# data_acqsation_system.net
KiCad netlist of a schematic drawn in EAGLE
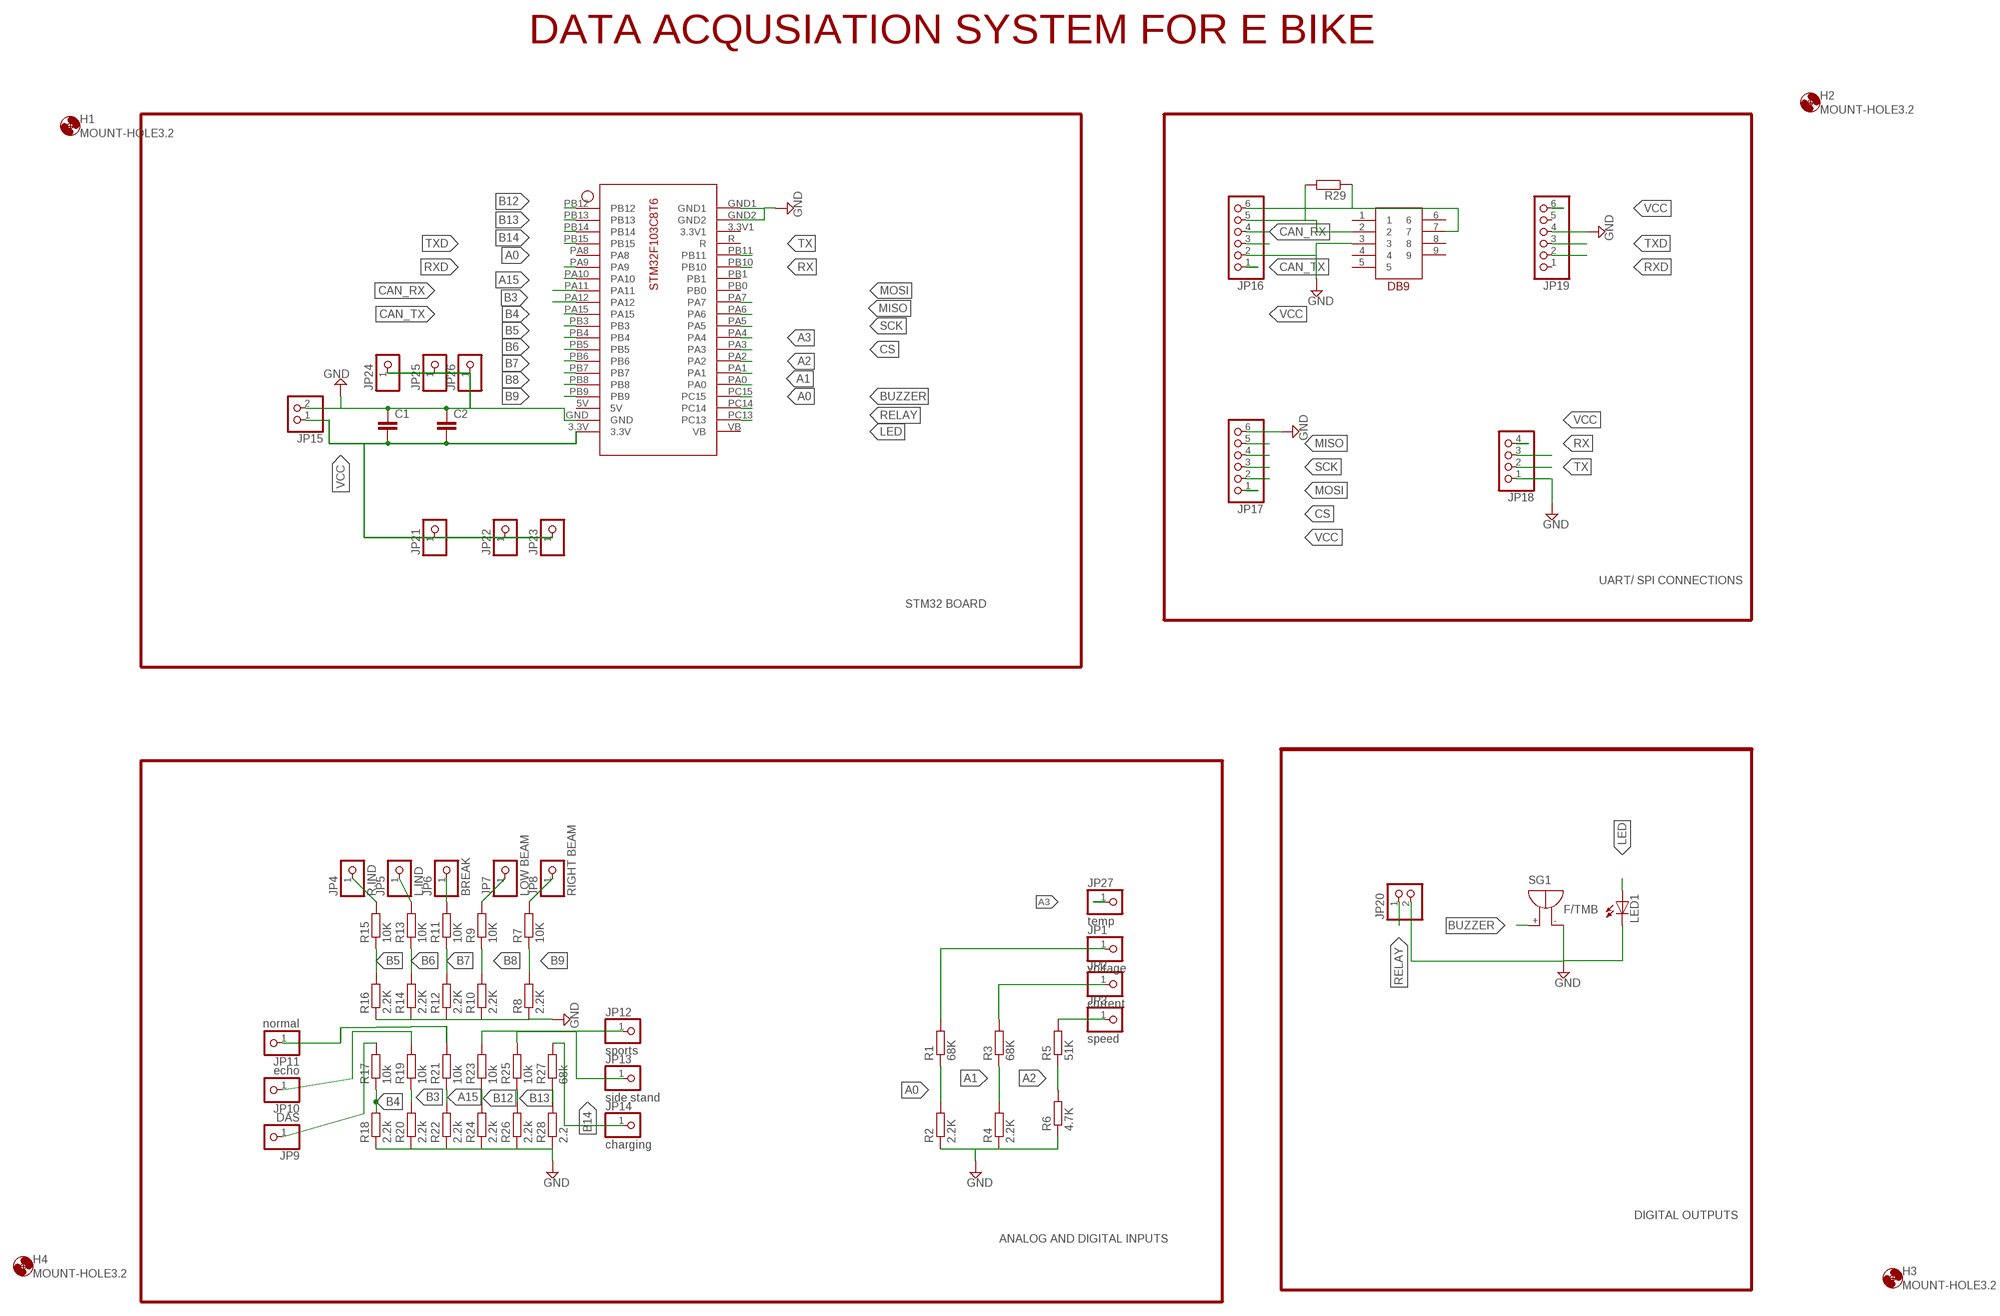
[diagram p0: schematic, sheet 1]

(export (version "E")
  (design (tool "Eeschema 10.0.6"))
  (components
    (comp (ref "C1")
      (value "C2.5/6")
      (footprint "eagle-import:C2.5-6")
      (libsource (lib "eagle-import") (part "C2.5/6"))
    )
    (comp (ref "C2")
      (value "C2.5/6")
      (footprint "eagle-import:C2.5-6")
      (libsource (lib "eagle-import") (part "C2.5/6"))
    )
    (comp (ref "H1")
      (value "MOUNT-HOLE3.2")
      (footprint "eagle-import:3,2")
      (libsource (lib "eagle-import") (part "MOUNT-HOLE3.2"))
    )
    (comp (ref "H2")
      (value "MOUNT-HOLE3.2")
      (footprint "eagle-import:3,2")
      (libsource (lib "eagle-import") (part "MOUNT-HOLE3.2"))
    )
    (comp (ref "H3")
      (value "MOUNT-HOLE3.2")
      (footprint "eagle-import:3,2")
      (libsource (lib "eagle-import") (part "MOUNT-HOLE3.2"))
    )
    (comp (ref "H4")
      (value "MOUNT-HOLE3.2")
      (footprint "eagle-import:3,2")
      (libsource (lib "eagle-import") (part "MOUNT-HOLE3.2"))
    )
    (comp (ref "JP1")
      (value "voltage")
      (footprint "eagle-import:1X01")
      (libsource (lib "eagle-import") (part "PINHD-1X1"))
    )
    (comp (ref "JP2")
      (value "current")
      (footprint "eagle-import:1X01")
      (libsource (lib "eagle-import") (part "PINHD-1X1"))
    )
    (comp (ref "JP3")
      (value "speed")
      (footprint "eagle-import:1X01")
      (libsource (lib "eagle-import") (part "PINHD-1X1"))
    )
    (comp (ref "JP4")
      (value "R.IND")
      (footprint "eagle-import:1X01")
      (libsource (lib "eagle-import") (part "PINHD-1X1"))
    )
    (comp (ref "JP5")
      (value "L.IND")
      (footprint "eagle-import:1X01")
      (libsource (lib "eagle-import") (part "PINHD-1X1"))
    )
    (comp (ref "JP6")
      (value "BREAK")
      (footprint "eagle-import:1X01")
      (libsource (lib "eagle-import") (part "PINHD-1X1"))
    )
    (comp (ref "JP7")
      (value "LOW BEAM")
      (footprint "eagle-import:1X01")
      (libsource (lib "eagle-import") (part "PINHD-1X1"))
    )
    (comp (ref "JP8")
      (value "RIGHT BEAM")
      (footprint "eagle-import:1X01")
      (libsource (lib "eagle-import") (part "PINHD-1X1"))
    )
    (comp (ref "JP9")
      (value "DAS")
      (footprint "eagle-import:1X01")
      (libsource (lib "eagle-import") (part "PINHD-1X1"))
    )
    (comp (ref "JP10")
      (value "echo")
      (footprint "eagle-import:1X01")
      (libsource (lib "eagle-import") (part "PINHD-1X1"))
    )
    (comp (ref "JP11")
      (value "normal")
      (footprint "eagle-import:1X01")
      (libsource (lib "eagle-import") (part "PINHD-1X1"))
    )
    (comp (ref "JP12")
      (value "sports")
      (footprint "eagle-import:1X01")
      (libsource (lib "eagle-import") (part "PINHD-1X1"))
    )
    (comp (ref "JP13")
      (value "side stand")
      (footprint "eagle-import:1X01")
      (libsource (lib "eagle-import") (part "PINHD-1X1"))
    )
    (comp (ref "JP14")
      (value "charging")
      (footprint "eagle-import:1X01")
      (libsource (lib "eagle-import") (part "PINHD-1X1"))
    )
    (comp (ref "JP15")
      (value "PINHD-1X2")
      (footprint "eagle-import:1X02")
      (libsource (lib "eagle-import") (part "PINHD-1X2"))
    )
    (comp (ref "JP16")
      (value "PINHD-1X6")
      (footprint "eagle-import:1X06")
      (libsource (lib "eagle-import") (part "PINHD-1X6"))
    )
    (comp (ref "JP17")
      (value "PINHD-1X6")
      (footprint "eagle-import:1X06")
      (libsource (lib "eagle-import") (part "PINHD-1X6"))
    )
    (comp (ref "JP18")
      (value "PINHD-1X4")
      (footprint "eagle-import:1X04")
      (libsource (lib "eagle-import") (part "PINHD-1X4"))
    )
    (comp (ref "JP19")
      (value "PINHD-1X6")
      (footprint "eagle-import:1X06")
      (libsource (lib "eagle-import") (part "PINHD-1X6"))
    )
    (comp (ref "JP20")
      (value "PINHD-1X2")
      (footprint "eagle-import:1X02")
      (libsource (lib "eagle-import") (part "PINHD-1X2"))
    )
    (comp (ref "JP21")
      (value "PINHD-1X1")
      (footprint "eagle-import:1X01")
      (libsource (lib "eagle-import") (part "PINHD-1X1"))
    )
    (comp (ref "JP22")
      (value "PINHD-1X1")
      (footprint "eagle-import:1X01")
      (libsource (lib "eagle-import") (part "PINHD-1X1"))
    )
    (comp (ref "JP23")
      (value "PINHD-1X1")
      (footprint "eagle-import:1X01")
      (libsource (lib "eagle-import") (part "PINHD-1X1"))
    )
    (comp (ref "JP24")
      (value "PINHD-1X1")
      (footprint "eagle-import:1X01")
      (libsource (lib "eagle-import") (part "PINHD-1X1"))
    )
    (comp (ref "JP25")
      (value "PINHD-1X1")
      (footprint "eagle-import:1X01")
      (libsource (lib "eagle-import") (part "PINHD-1X1"))
    )
    (comp (ref "JP26")
      (value "PINHD-1X1")
      (footprint "eagle-import:1X01")
      (libsource (lib "eagle-import") (part "PINHD-1X1"))
    )
    (comp (ref "JP27")
      (value "temp")
      (footprint "eagle-import:1X01")
      (libsource (lib "eagle-import") (part "PINHD-1X1"))
    )
    (comp (ref "LED1")
      (value "LED5MM")
      (footprint "eagle-import:LED5MM")
      (libsource (lib "eagle-import") (part "LED5MM"))
    )
    (comp (ref "R1")
      (value "68K")
      (footprint "eagle-import:0309_12")
      (libsource (lib "eagle-import") (part "R-EU_0309/12"))
    )
    (comp (ref "R2")
      (value "2.2K")
      (footprint "eagle-import:0309_12")
      (libsource (lib "eagle-import") (part "R-EU_0309/12"))
    )
    (comp (ref "R3")
      (value "68K")
      (footprint "eagle-import:0309_12")
      (libsource (lib "eagle-import") (part "R-EU_0309/12"))
    )
    (comp (ref "R4")
      (value "2.2K")
      (footprint "eagle-import:0309_12")
      (libsource (lib "eagle-import") (part "R-EU_0309/12"))
    )
    (comp (ref "R5")
      (value "51K")
      (footprint "eagle-import:0309_12")
      (libsource (lib "eagle-import") (part "R-EU_0309/12"))
    )
    (comp (ref "R6")
      (value "4.7K")
      (footprint "eagle-import:0309_12")
      (libsource (lib "eagle-import") (part "R-EU_0309/12"))
    )
    (comp (ref "R7")
      (value "10K")
      (footprint "eagle-import:0309_12")
      (libsource (lib "eagle-import") (part "R-EU_0309/12"))
    )
    (comp (ref "R8")
      (value "2.2K")
      (footprint "eagle-import:0309_12")
      (libsource (lib "eagle-import") (part "R-EU_0309/12"))
    )
    (comp (ref "R9")
      (value "10K")
      (footprint "eagle-import:0309_12")
      (libsource (lib "eagle-import") (part "R-EU_0309/12"))
    )
    (comp (ref "R10")
      (value "2.2K")
      (footprint "eagle-import:0309_12")
      (libsource (lib "eagle-import") (part "R-EU_0309/12"))
    )
    (comp (ref "R11")
      (value "10K")
      (footprint "eagle-import:0309_12")
      (libsource (lib "eagle-import") (part "R-EU_0309/12"))
    )
    (comp (ref "R12")
      (value "2.2K")
      (footprint "eagle-import:0309_12")
      (libsource (lib "eagle-import") (part "R-EU_0309/12"))
    )
    (comp (ref "R13")
      (value "10K")
      (footprint "eagle-import:0309_12")
      (libsource (lib "eagle-import") (part "R-EU_0309/12"))
    )
    (comp (ref "R14")
      (value "2.2K")
      (footprint "eagle-import:0309_12")
      (libsource (lib "eagle-import") (part "R-EU_0309/12"))
    )
    (comp (ref "R15")
      (value "10K")
      (footprint "eagle-import:0309_12")
      (libsource (lib "eagle-import") (part "R-EU_0309/12"))
    )
    (comp (ref "R16")
      (value "2.2K")
      (footprint "eagle-import:0309_12")
      (libsource (lib "eagle-import") (part "R-EU_0309/12"))
    )
    (comp (ref "R17")
      (value "10k")
      (footprint "eagle-import:0309_12")
      (libsource (lib "eagle-import") (part "R-EU_0309/12"))
    )
    (comp (ref "R18")
      (value "2.2k")
      (footprint "eagle-import:0309_12")
      (libsource (lib "eagle-import") (part "R-EU_0309/12"))
    )
    (comp (ref "R19")
      (value "10k")
      (footprint "eagle-import:0309_12")
      (libsource (lib "eagle-import") (part "R-EU_0309/12"))
    )
    (comp (ref "R20")
      (value "2.2k")
      (footprint "eagle-import:0309_12")
      (libsource (lib "eagle-import") (part "R-EU_0309/12"))
    )
    (comp (ref "R21")
      (value "10k")
      (footprint "eagle-import:0309_12")
      (libsource (lib "eagle-import") (part "R-EU_0309/12"))
    )
    (comp (ref "R22")
      (value "2.2k")
      (footprint "eagle-import:0309_12")
      (libsource (lib "eagle-import") (part "R-EU_0309/12"))
    )
    (comp (ref "R23")
      (value "10k")
      (footprint "eagle-import:0309_12")
      (libsource (lib "eagle-import") (part "R-EU_0309/12"))
    )
    (comp (ref "R24")
      (value "2.2k")
      (footprint "eagle-import:0309_12")
      (libsource (lib "eagle-import") (part "R-EU_0309/12"))
    )
    (comp (ref "R25")
      (value "10k")
      (footprint "eagle-import:0309_12")
      (libsource (lib "eagle-import") (part "R-EU_0309/12"))
    )
    (comp (ref "R26")
      (value "2.2k")
      (footprint "eagle-import:0309_12")
      (libsource (lib "eagle-import") (part "R-EU_0309/12"))
    )
    (comp (ref "R27")
      (value "68k")
      (footprint "eagle-import:0309_12")
      (libsource (lib "eagle-import") (part "R-EU_0309/12"))
    )
    (comp (ref "R28")
      (value "2.2")
      (footprint "eagle-import:0309_12")
      (libsource (lib "eagle-import") (part "R-EU_0309/12"))
    )
    (comp (ref "R29")
      (value "R-EU_0309/12")
      (footprint "eagle-import:0309_12")
      (libsource (lib "eagle-import") (part "R-EU_0309/12"))
    )
    (comp (ref "SG1")
      (value "F/TMB")
      (footprint "eagle-import:F_TMB")
      (libsource (lib "eagle-import") (part "F/TMB"))
    )
    (comp (ref "U$1")
      (value "STM32F103C8T6")
      (footprint "eagle-import:STM32F103C8T6")
      (libsource (lib "eagle-import") (part "STM32F103C8T6"))
    )
    (comp (ref "U$2")
      (value "DB9")
      (footprint "eagle-import:DB9")
      (libsource (lib "eagle-import") (part "DB9"))
    )
  )
  (nets
    (net (code "1") (name "A0") (class "Default")
      (node (ref "R1") (pin "1") (pinfunction "1_1") (pintype "passive"))
      (node (ref "R2") (pin "2") (pinfunction "2_2") (pintype "passive"))
      (node (ref "U$1") (pin "PA0") (pinfunction "PA0_PA0") (pintype "bidirectional"))
      (node (ref "U$1") (pin "PB15") (pinfunction "PB15_PB15") (pintype "bidirectional"))
    )
    (net (code "2") (name "A1") (class "Default")
      (node (ref "R3") (pin "1") (pinfunction "1_1") (pintype "passive"))
      (node (ref "R4") (pin "2") (pinfunction "2_2") (pintype "passive"))
      (node (ref "U$1") (pin "PA1") (pinfunction "PA1_PA1") (pintype "bidirectional"))
    )
    (net (code "3") (name "A2") (class "Default")
      (node (ref "R5") (pin "1") (pinfunction "1_1") (pintype "passive"))
      (node (ref "R6") (pin "2") (pinfunction "2_2") (pintype "passive"))
      (node (ref "U$1") (pin "PA2") (pinfunction "PA2_PA2") (pintype "bidirectional"))
    )
    (net (code "4") (name "A3") (class "Default")
      (node (ref "JP27") (pin "1") (pinfunction "1_1") (pintype "passive"))
      (node (ref "U$1") (pin "PA4") (pinfunction "PA4_PA4") (pintype "bidirectional"))
    )
    (net (code "5") (name "A15") (class "Default")
      (node (ref "R21") (pin "1") (pinfunction "1_1") (pintype "passive"))
      (node (ref "R22") (pin "2") (pinfunction "2_2") (pintype "passive"))
      (node (ref "U$1") (pin "PA15") (pinfunction "PA15_PA15") (pintype "bidirectional"))
    )
    (net (code "6") (name "B3") (class "Default")
      (node (ref "R19") (pin "1") (pinfunction "1_1") (pintype "passive"))
      (node (ref "R20") (pin "2") (pinfunction "2_2") (pintype "passive"))
      (node (ref "U$1") (pin "PB3") (pinfunction "PB3_PB3") (pintype "bidirectional"))
    )
    (net (code "7") (name "B4") (class "Default")
      (node (ref "R17") (pin "1") (pinfunction "1_1") (pintype "passive"))
      (node (ref "R18") (pin "2") (pinfunction "2_2") (pintype "passive"))
      (node (ref "U$1") (pin "PB4") (pinfunction "PB4_PB4") (pintype "bidirectional"))
    )
    (net (code "8") (name "B5") (class "Default")
      (node (ref "R15") (pin "1") (pinfunction "1_1") (pintype "passive"))
      (node (ref "R16") (pin "2") (pinfunction "2_2") (pintype "passive"))
      (node (ref "U$1") (pin "PB5") (pinfunction "PB5_PB5") (pintype "bidirectional"))
    )
    (net (code "9") (name "B6") (class "Default")
      (node (ref "R13") (pin "1") (pinfunction "1_1") (pintype "passive"))
      (node (ref "R14") (pin "2") (pinfunction "2_2") (pintype "passive"))
      (node (ref "U$1") (pin "PB6") (pinfunction "PB6_PB6") (pintype "bidirectional"))
    )
    (net (code "10") (name "B7") (class "Default")
      (node (ref "R11") (pin "1") (pinfunction "1_1") (pintype "passive"))
      (node (ref "R12") (pin "2") (pinfunction "2_2") (pintype "passive"))
      (node (ref "U$1") (pin "PB7") (pinfunction "PB7_PB7") (pintype "bidirectional"))
    )
    (net (code "11") (name "B8") (class "Default")
      (node (ref "R10") (pin "2") (pinfunction "2_2") (pintype "passive"))
      (node (ref "R9") (pin "1") (pinfunction "1_1") (pintype "passive"))
      (node (ref "U$1") (pin "PB8") (pinfunction "PB8_PB8") (pintype "bidirectional"))
    )
    (net (code "12") (name "B9") (class "Default")
      (node (ref "R7") (pin "1") (pinfunction "1_1") (pintype "passive"))
      (node (ref "R8") (pin "2") (pinfunction "2_2") (pintype "passive"))
      (node (ref "U$1") (pin "PB9") (pinfunction "PB9_PB9") (pintype "bidirectional"))
    )
    (net (code "13") (name "B12") (class "Default")
      (node (ref "R23") (pin "1") (pinfunction "1_1") (pintype "passive"))
      (node (ref "R24") (pin "2") (pinfunction "2_2") (pintype "passive"))
      (node (ref "U$1") (pin "PB12") (pinfunction "PB12_PB12") (pintype "bidirectional"))
    )
    (net (code "14") (name "B13") (class "Default")
      (node (ref "R25") (pin "1") (pinfunction "1_1") (pintype "passive"))
      (node (ref "R26") (pin "2") (pinfunction "2_2") (pintype "passive"))
      (node (ref "U$1") (pin "PB13") (pinfunction "PB13_PB13") (pintype "bidirectional"))
    )
    (net (code "15") (name "B14") (class "Default")
      (node (ref "R27") (pin "1") (pinfunction "1_1") (pintype "passive"))
      (node (ref "R28") (pin "2") (pinfunction "2_2") (pintype "passive"))
      (node (ref "U$1") (pin "PB14") (pinfunction "PB14_PB14") (pintype "bidirectional"))
    )
    (net (code "16") (name "BUZZER") (class "Default")
      (node (ref "SG1") (pin "+") (pinfunction "+_+") (pintype "passive"))
      (node (ref "U$1") (pin "PC15") (pinfunction "PC15_PC15") (pintype "bidirectional"))
    )
    (net (code "17") (name "CAN_RX") (class "Default")
      (node (ref "JP16") (pin "4") (pinfunction "4_4") (pintype "passive"))
      (node (ref "U$1") (pin "PA11") (pinfunction "PA11_PA11") (pintype "bidirectional"))
    )
    (net (code "18") (name "CAN_TX") (class "Default")
      (node (ref "JP16") (pin "3") (pinfunction "3_3") (pintype "passive"))
      (node (ref "U$1") (pin "PA12") (pinfunction "PA12_PA12") (pintype "bidirectional"))
    )
    (net (code "19") (name "CS") (class "Default")
      (node (ref "JP17") (pin "2") (pinfunction "2_2") (pintype "passive"))
      (node (ref "U$1") (pin "PA3") (pinfunction "PA3_PA3") (pintype "bidirectional"))
    )
    (net (code "20") (name "GND") (class "Default")
      (node (ref "C1") (pin "1") (pinfunction "1_1") (pintype "passive"))
      (node (ref "C2") (pin "1") (pinfunction "1_1") (pintype "passive"))
      (node (ref "JP15") (pin "2") (pinfunction "2_2") (pintype "passive"))
      (node (ref "JP16") (pin "2") (pinfunction "2_2") (pintype "passive"))
      (node (ref "JP17") (pin "6") (pinfunction "6_6") (pintype "passive"))
      (node (ref "JP18") (pin "1") (pinfunction "1_1") (pintype "passive"))
      (node (ref "JP19") (pin "4") (pinfunction "4_4") (pintype "passive"))
      (node (ref "JP20") (pin "2") (pinfunction "2_2") (pintype "passive"))
      (node (ref "JP24") (pin "1") (pinfunction "1_1") (pintype "passive"))
      (node (ref "JP25") (pin "1") (pinfunction "1_1") (pintype "passive"))
      (node (ref "JP26") (pin "1") (pinfunction "1_1") (pintype "passive"))
      (node (ref "LED1") (pin "K") (pinfunction "C_K") (pintype "passive"))
      (node (ref "R10") (pin "1") (pinfunction "1_1") (pintype "passive"))
      (node (ref "R12") (pin "1") (pinfunction "1_1") (pintype "passive"))
      (node (ref "R14") (pin "1") (pinfunction "1_1") (pintype "passive"))
      (node (ref "R16") (pin "1") (pinfunction "1_1") (pintype "passive"))
      (node (ref "R18") (pin "1") (pinfunction "1_1") (pintype "passive"))
      (node (ref "R2") (pin "1") (pinfunction "1_1") (pintype "passive"))
      (node (ref "R20") (pin "1") (pinfunction "1_1") (pintype "passive"))
      (node (ref "R22") (pin "1") (pinfunction "1_1") (pintype "passive"))
      (node (ref "R24") (pin "1") (pinfunction "1_1") (pintype "passive"))
      (node (ref "R26") (pin "1") (pinfunction "1_1") (pintype "passive"))
      (node (ref "R28") (pin "1") (pinfunction "1_1") (pintype "passive"))
      (node (ref "R4") (pin "1") (pinfunction "1_1") (pintype "passive"))
      (node (ref "R6") (pin "1") (pinfunction "1_1") (pintype "passive"))
      (node (ref "R8") (pin "1") (pinfunction "1_1") (pintype "passive"))
      (node (ref "SG1") (pin "-") (pinfunction "-_-") (pintype "passive"))
      (node (ref "U$1") (pin "GND") (pinfunction "GND_GND") (pintype "bidirectional"))
      (node (ref "U$1") (pin "GND1") (pinfunction "GND1_GND1") (pintype "bidirectional"))
      (node (ref "U$1") (pin "GND2") (pinfunction "GND2_GND2") (pintype "bidirectional"))
      (node (ref "U$2") (pin "3") (pinfunction "3_3") (pintype "bidirectional"))
    )
    (net (code "21") (name "LED") (class "Default")
      (node (ref "LED1") (pin "A") (pinfunction "A_A") (pintype "passive"))
      (node (ref "U$1") (pin "PC13") (pinfunction "PC13_PC13") (pintype "bidirectional"))
    )
    (net (code "22") (name "MISO") (class "Default")
      (node (ref "JP17") (pin "5") (pinfunction "5_5") (pintype "passive"))
      (node (ref "U$1") (pin "PA6") (pinfunction "PA6_PA6") (pintype "bidirectional"))
    )
    (net (code "23") (name "MOSI") (class "Default")
      (node (ref "JP17") (pin "3") (pinfunction "3_3") (pintype "passive"))
      (node (ref "U$1") (pin "PA7") (pinfunction "PA7_PA7") (pintype "bidirectional"))
    )
    (net (code "24") (name "Net-(JP1-Pad1)") (class "Default")
      (node (ref "JP1") (pin "1") (pinfunction "1_1") (pintype "passive"))
      (node (ref "R1") (pin "2") (pinfunction "2_2") (pintype "passive"))
    )
    (net (code "25") (name "Net-(JP2-Pad1)") (class "Default")
      (node (ref "JP2") (pin "1") (pinfunction "1_1") (pintype "passive"))
      (node (ref "R3") (pin "2") (pinfunction "2_2") (pintype "passive"))
    )
    (net (code "26") (name "Net-(JP3-Pad1)") (class "Default")
      (node (ref "JP3") (pin "1") (pinfunction "1_1") (pintype "passive"))
      (node (ref "R5") (pin "2") (pinfunction "2_2") (pintype "passive"))
    )
    (net (code "27") (name "Net-(JP4-Pad1)") (class "Default")
      (node (ref "JP4") (pin "1") (pinfunction "1_1") (pintype "passive"))
      (node (ref "R15") (pin "2") (pinfunction "2_2") (pintype "passive"))
    )
    (net (code "28") (name "Net-(JP5-Pad1)") (class "Default")
      (node (ref "JP5") (pin "1") (pinfunction "1_1") (pintype "passive"))
      (node (ref "R13") (pin "2") (pinfunction "2_2") (pintype "passive"))
    )
    (net (code "29") (name "Net-(JP6-Pad1)") (class "Default")
      (node (ref "JP6") (pin "1") (pinfunction "1_1") (pintype "passive"))
      (node (ref "R11") (pin "2") (pinfunction "2_2") (pintype "passive"))
    )
    (net (code "30") (name "Net-(JP7-Pad1)") (class "Default")
      (node (ref "JP7") (pin "1") (pinfunction "1_1") (pintype "passive"))
      (node (ref "R9") (pin "2") (pinfunction "2_2") (pintype "passive"))
    )
    (net (code "31") (name "Net-(JP8-Pad1)") (class "Default")
      (node (ref "JP8") (pin "1") (pinfunction "1_1") (pintype "passive"))
      (node (ref "R7") (pin "2") (pinfunction "2_2") (pintype "passive"))
    )
    (net (code "32") (name "Net-(JP9-Pad1)") (class "Default")
      (node (ref "JP9") (pin "1") (pinfunction "1_1") (pintype "passive"))
      (node (ref "R17") (pin "2") (pinfunction "2_2") (pintype "passive"))
    )
    (net (code "33") (name "Net-(JP10-Pad1)") (class "Default")
      (node (ref "JP10") (pin "1") (pinfunction "1_1") (pintype "passive"))
      (node (ref "R19") (pin "2") (pinfunction "2_2") (pintype "passive"))
    )
    (net (code "34") (name "Net-(JP11-Pad1)") (class "Default")
      (node (ref "JP11") (pin "1") (pinfunction "1_1") (pintype "passive"))
      (node (ref "R21") (pin "2") (pinfunction "2_2") (pintype "passive"))
    )
    (net (code "35") (name "Net-(JP12-Pad1)") (class "Default")
      (node (ref "JP12") (pin "1") (pinfunction "1_1") (pintype "passive"))
      (node (ref "R23") (pin "2") (pinfunction "2_2") (pintype "passive"))
    )
    (net (code "36") (name "Net-(JP13-Pad1)") (class "Default")
      (node (ref "JP13") (pin "1") (pinfunction "1_1") (pintype "passive"))
      (node (ref "R25") (pin "2") (pinfunction "2_2") (pintype "passive"))
    )
    (net (code "37") (name "Net-(JP14-Pad1)") (class "Default")
      (node (ref "JP14") (pin "1") (pinfunction "1_1") (pintype "passive"))
      (node (ref "R27") (pin "2") (pinfunction "2_2") (pintype "passive"))
    )
    (net (code "38") (name "Net-(JP16-Pad5)") (class "Default")
      (node (ref "JP16") (pin "5") (pinfunction "5_5") (pintype "passive"))
      (node (ref "R29") (pin "2") (pinfunction "2_2") (pintype "passive"))
      (node (ref "U$2") (pin "2") (pinfunction "2_2") (pintype "bidirectional"))
    )
    (net (code "39") (name "Net-(JP16-Pad6)") (class "Default")
      (node (ref "JP16") (pin "6") (pinfunction "6_6") (pintype "passive"))
      (node (ref "R29") (pin "1") (pinfunction "1_1") (pintype "passive"))
      (node (ref "U$2") (pin "7") (pinfunction "7_7") (pintype "bidirectional"))
    )
    (net (code "40") (name "RELAY") (class "Default")
      (node (ref "JP20") (pin "1") (pinfunction "1_1") (pintype "passive"))
      (node (ref "U$1") (pin "PC14") (pinfunction "PC14_PC14") (pintype "bidirectional"))
    )
    (net (code "41") (name "RX") (class "Default")
      (node (ref "JP18") (pin "3") (pinfunction "3_3") (pintype "passive"))
      (node (ref "U$1") (pin "PB10") (pinfunction "PB10_PB10") (pintype "bidirectional"))
    )
    (net (code "42") (name "RXD") (class "Default")
      (node (ref "JP19") (pin "2") (pinfunction "2_2") (pintype "passive"))
      (node (ref "U$1") (pin "PA10") (pinfunction "PA10_PA10") (pintype "bidirectional"))
    )
    (net (code "43") (name "SCK") (class "Default")
      (node (ref "JP17") (pin "4") (pinfunction "4_4") (pintype "passive"))
      (node (ref "U$1") (pin "PA5") (pinfunction "PA5_PA5") (pintype "bidirectional"))
    )
    (net (code "44") (name "TX") (class "Default")
      (node (ref "JP18") (pin "2") (pinfunction "2_2") (pintype "passive"))
      (node (ref "U$1") (pin "PB11") (pinfunction "PB11_PB11") (pintype "bidirectional"))
    )
    (net (code "45") (name "TXD") (class "Default")
      (node (ref "JP19") (pin "3") (pinfunction "3_3") (pintype "passive"))
      (node (ref "U$1") (pin "PA9") (pinfunction "PA9_PA9") (pintype "bidirectional"))
    )
    (net (code "46") (name "VCC") (class "Default")
      (node (ref "C1") (pin "2") (pinfunction "2_2") (pintype "passive"))
      (node (ref "C2") (pin "2") (pinfunction "2_2") (pintype "passive"))
      (node (ref "JP15") (pin "1") (pinfunction "1_1") (pintype "passive"))
      (node (ref "JP16") (pin "1") (pinfunction "1_1") (pintype "passive"))
      (node (ref "JP17") (pin "1") (pinfunction "1_1") (pintype "passive"))
      (node (ref "JP18") (pin "4") (pinfunction "4_4") (pintype "passive"))
      (node (ref "JP19") (pin "6") (pinfunction "6_6") (pintype "passive"))
      (node (ref "JP21") (pin "1") (pinfunction "1_1") (pintype "passive"))
      (node (ref "JP22") (pin "1") (pinfunction "1_1") (pintype "passive"))
      (node (ref "JP23") (pin "1") (pinfunction "1_1") (pintype "passive"))
      (node (ref "U$1") (pin "3.3V") (pinfunction "3.3V_3.3V") (pintype "bidirectional"))
    )
    (net (code "47") (name "unconnected-(JP19-Pad1)") (class "Default")
      (node (ref "JP19") (pin "1") (pinfunction "1_1") (pintype "passive"))
    )
    (net (code "48") (name "unconnected-(JP19-Pad5)") (class "Default")
      (node (ref "JP19") (pin "5") (pinfunction "5_5") (pintype "passive"))
    )
    (net (code "49") (name "unconnected-(U$1-Pad3.3V1)") (class "Default")
      (node (ref "U$1") (pin "3.3V1") (pinfunction "3.3V1_3.3V1") (pintype "bidirectional"))
    )
    (net (code "50") (name "unconnected-(U$1-Pad5V)") (class "Default")
      (node (ref "U$1") (pin "5V") (pinfunction "5V_5V") (pintype "bidirectional"))
    )
    (net (code "51") (name "unconnected-(U$1-PadPA8)") (class "Default")
      (node (ref "U$1") (pin "PA8") (pinfunction "PA8_PA8") (pintype "bidirectional"))
    )
    (net (code "52") (name "unconnected-(U$1-PadPB0)") (class "Default")
      (node (ref "U$1") (pin "PB0") (pinfunction "PB0_PB0") (pintype "bidirectional"))
    )
    (net (code "53") (name "unconnected-(U$1-PadPB1)") (class "Default")
      (node (ref "U$1") (pin "PB1") (pinfunction "PB1_PB1") (pintype "bidirectional"))
    )
    (net (code "54") (name "unconnected-(U$1-PadR)") (class "Default")
      (node (ref "U$1") (pin "R") (pinfunction "R_R") (pintype "bidirectional"))
    )
    (net (code "55") (name "unconnected-(U$1-PadVB)") (class "Default")
      (node (ref "U$1") (pin "VB") (pinfunction "VB_VB") (pintype "bidirectional"))
    )
    (net (code "56") (name "unconnected-(U$2-Pad1)") (class "Default")
      (node (ref "U$2") (pin "1") (pinfunction "1_1") (pintype "bidirectional"))
    )
    (net (code "57") (name "unconnected-(U$2-Pad4)") (class "Default")
      (node (ref "U$2") (pin "4") (pinfunction "4_4") (pintype "bidirectional"))
    )
    (net (code "58") (name "unconnected-(U$2-Pad5)") (class "Default")
      (node (ref "U$2") (pin "5") (pinfunction "5_5") (pintype "bidirectional"))
    )
    (net (code "59") (name "unconnected-(U$2-Pad6)") (class "Default")
      (node (ref "U$2") (pin "6") (pinfunction "6_6") (pintype "bidirectional"))
    )
    (net (code "60") (name "unconnected-(U$2-Pad8)") (class "Default")
      (node (ref "U$2") (pin "8") (pinfunction "8_8") (pintype "bidirectional"))
    )
    (net (code "61") (name "unconnected-(U$2-Pad9)") (class "Default")
      (node (ref "U$2") (pin "9") (pinfunction "9_9") (pintype "bidirectional"))
    )
  )
)
